# CONVERTER.net
KiCad netlist of a schematic drawn in Altium Designer
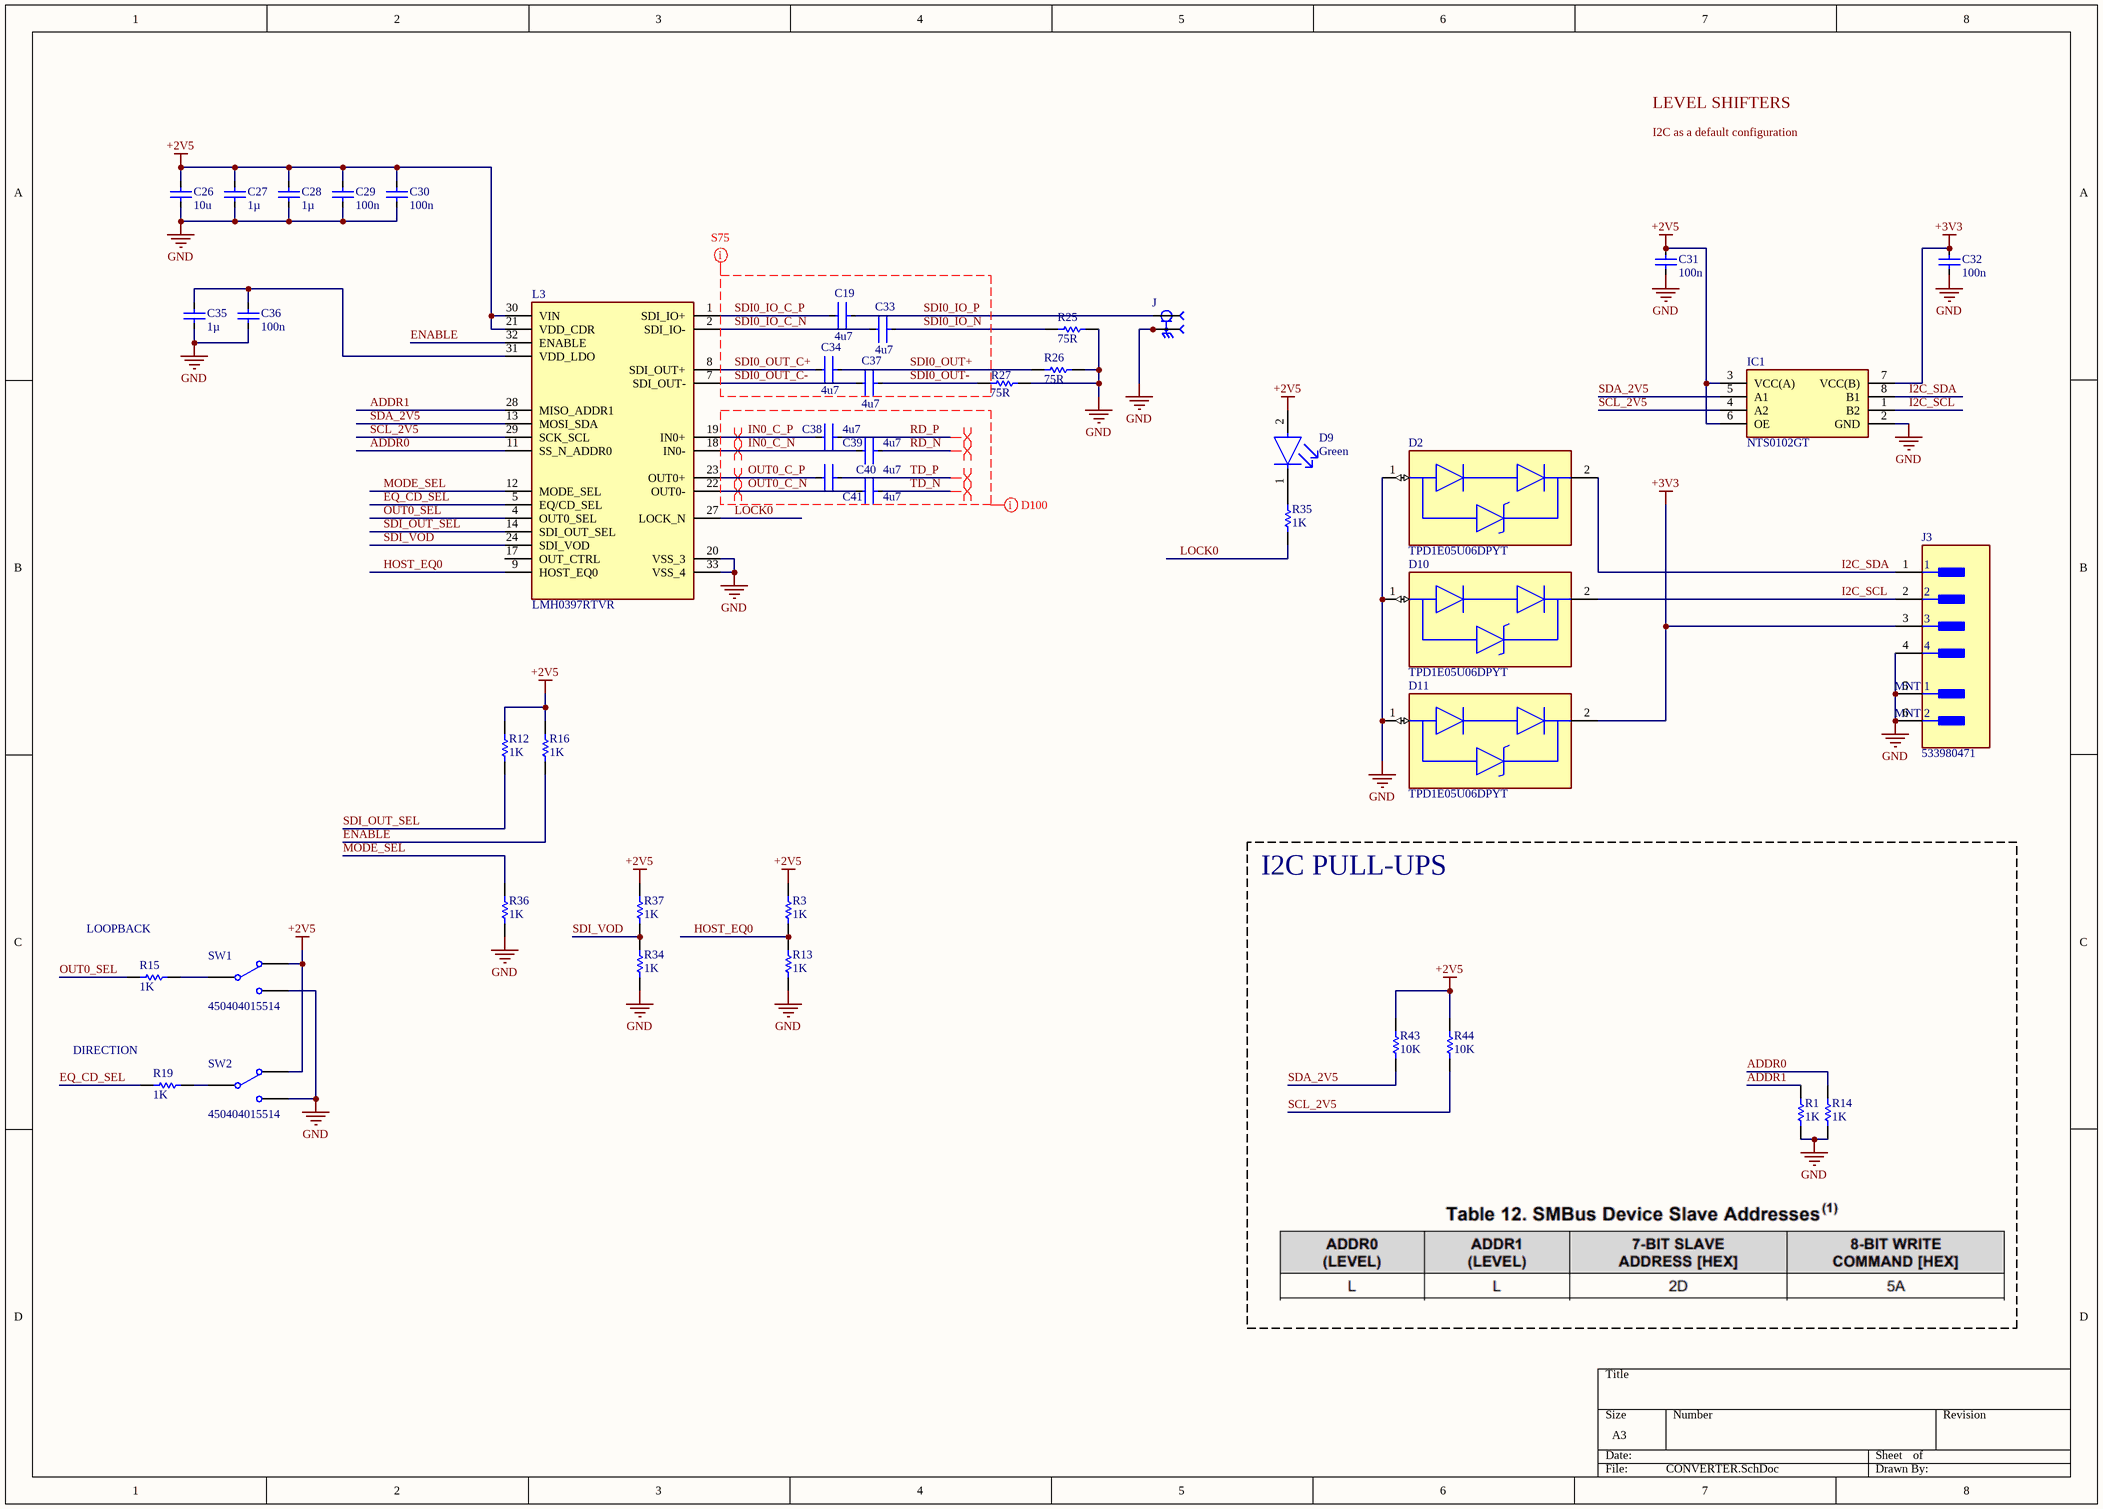
[diagram p0: CONVERTER.SchDoc]

(export (version "E")
  (design (tool "Eeschema 10.0.6"))
  (components
    (comp (ref "C19")
      (value "4u7")
      (footprint "FP-GRM155-0_1-MFG")
      (description "Chip Multilayer Ceramic Capacitors for General Purpose, 0402, 4.7uF, X5R, 15%, 20%, 6.3V")
      (fields (field (name "VOLTAGE") "6.3V") (field (name "TOLERANCE") "20%"))
      (libsource (lib "Altium Content Vault") (part "11868f565c42a9108669ba33697ecf6"))
    )
    (comp (ref "C26")
      (value "10u")
      (footprint "FP-C1608-080-0_1-IPC_C")
      (description "MLCC 10μF ±10% 6.3V JB SMD 0603")
      (fields (field (name "TOLERANCE") "10%") (field (name "Comment") "C1608JB0J106K080AB"))
      (libsource (lib "Schlib1") (part "C1608JB0J106K080AB"))
    )
    (comp (ref "C27")
      (value "1µ")
      (footprint "pcblib1:CAPC1005X55X10NL05")
      (description "MLCC 1 uF, +/- 10%, 10 V, -55 to 85 degC, 0402 (1005 Metric), RoHS, Tape and Reel")
      (fields (field (name "MANUFACTURER") "TDK") (field (name "TOLERANCE") "±10%"))
      (libsource (lib "Schlib1") (part "C1005X5R1A105K050BB"))
    )
    (comp (ref "C28")
      (value "1µ")
      (footprint "pcblib1:CAPC1005X55X10NL05")
      (description "MLCC 1 uF, +/- 10%, 10 V, -55 to 85 degC, 0402 (1005 Metric), RoHS, Tape and Reel")
      (fields (field (name "MANUFACTURER") "TDK") (field (name "TOLERANCE") "±10%"))
      (libsource (lib "Schlib1") (part "C1005X5R1A105K050BB"))
    )
    (comp (ref "C29")
      (value "100n")
      (footprint "FP-C1005-050-0_05-IPC_C")
      (description "MLCC 100nF ±10% 50V X7R SMD 0402")
      (fields (field (name "VOLTAGE") "50V") (field (name "TOLERANCE") "10%"))
      (libsource (lib "Schlib1") (part "C1005X7R1H104K050BB"))
    )
    (comp (ref "C30")
      (value "100n")
      (footprint "FP-C1005-050-0_05-IPC_C")
      (description "MLCC 100nF ±10% 50V X7R SMD 0402")
      (fields (field (name "VOLTAGE") "50V") (field (name "TOLERANCE") "10%"))
      (libsource (lib "Schlib1") (part "C1005X7R1H104K050BB"))
    )
    (comp (ref "C31")
      (value "100n")
      (footprint "FP-C1005-050-0_05-IPC_C")
      (description "MLCC 100nF ±10% 50V X7R SMD 0402")
      (fields (field (name "VOLTAGE") "50V") (field (name "TOLERANCE") "10%"))
      (libsource (lib "Schlib1") (part "C1005X7R1H104K050BB"))
    )
    (comp (ref "C32")
      (value "100n")
      (footprint "FP-C1005-050-0_05-IPC_C")
      (description "MLCC 100nF ±10% 50V X7R SMD 0402")
      (fields (field (name "VOLTAGE") "50V") (field (name "TOLERANCE") "10%"))
      (libsource (lib "Schlib1") (part "C1005X7R1H104K050BB"))
    )
    (comp (ref "C33")
      (value "4u7")
      (footprint "FP-GRM155-0_1-MFG")
      (description "Chip Multilayer Ceramic Capacitors for General Purpose, 0402, 4.7uF, X5R, 15%, 20%, 6.3V")
      (fields (field (name "VOLTAGE") "6.3V") (field (name "TOLERANCE") "20%"))
      (libsource (lib "Altium Content Vault") (part "11868f565c42a9108669ba33697ecf6"))
    )
    (comp (ref "C34")
      (value "4u7")
      (footprint "FP-GRM155-0_1-MFG")
      (description "Chip Multilayer Ceramic Capacitors for General Purpose, 0402, 4.7uF, X5R, 15%, 20%, 6.3V")
      (fields (field (name "VOLTAGE") "6.3V") (field (name "TOLERANCE") "20%"))
      (libsource (lib "Altium Content Vault") (part "11868f565c42a9108669ba33697ecf6"))
    )
    (comp (ref "C35")
      (value "1µ")
      (footprint "pcblib1:CAPC1005X55X10NL05")
      (description "MLCC 1 uF, +/- 10%, 10 V, -55 to 85 degC, 0402 (1005 Metric), RoHS, Tape and Reel")
      (fields (field (name "MANUFACTURER") "TDK") (field (name "TOLERANCE") "±10%"))
      (libsource (lib "Schlib1") (part "C1005X5R1A105K050BB"))
    )
    (comp (ref "C36")
      (value "100n")
      (footprint "FP-C1005-050-0_05-IPC_C")
      (description "MLCC 100nF ±10% 50V X7R SMD 0402")
      (fields (field (name "VOLTAGE") "50V") (field (name "TOLERANCE") "10%"))
      (libsource (lib "Schlib1") (part "C1005X7R1H104K050BB"))
    )
    (comp (ref "C37")
      (value "4u7")
      (footprint "FP-GRM155-0_1-MFG")
      (description "Chip Multilayer Ceramic Capacitors for General Purpose, 0402, 4.7uF, X5R, 15%, 20%, 6.3V")
      (fields (field (name "VOLTAGE") "6.3V") (field (name "TOLERANCE") "20%"))
      (libsource (lib "Altium Content Vault") (part "11868f565c42a9108669ba33697ecf6"))
    )
    (comp (ref "C38")
      (value "4u7")
      (footprint "FP-GRM155-0_1-IPC_B")
      (description "Chip Multilayer Ceramic Capacitors for General Purpose, 0402, 4.7uF, X5R, 15%, 20%, 6.3V")
      (fields (field (name "VOLTAGE") "6.3V") (field (name "TOLERANCE") "20%"))
      (libsource (lib "Altium Content Vault") (part "11868f565c42a9108669ba33697ecf6"))
    )
    (comp (ref "C39")
      (value "4u7")
      (footprint "FP-GRM155-0_1-IPC_B")
      (description "Chip Multilayer Ceramic Capacitors for General Purpose, 0402, 4.7uF, X5R, 15%, 20%, 6.3V")
      (fields (field (name "VOLTAGE") "6.3V") (field (name "TOLERANCE") "20%"))
      (libsource (lib "Altium Content Vault") (part "11868f565c42a9108669ba33697ecf6"))
    )
    (comp (ref "C40")
      (value "4u7")
      (footprint "FP-GRM155-0_1-IPC_B")
      (description "Chip Multilayer Ceramic Capacitors for General Purpose, 0402, 4.7uF, X5R, 15%, 20%, 6.3V")
      (fields (field (name "VOLTAGE") "6.3V") (field (name "TOLERANCE") "20%"))
      (libsource (lib "Altium Content Vault") (part "11868f565c42a9108669ba33697ecf6"))
    )
    (comp (ref "C41")
      (value "4u7")
      (footprint "FP-GRM155-0_1-IPC_B")
      (description "Chip Multilayer Ceramic Capacitors for General Purpose, 0402, 4.7uF, X5R, 15%, 20%, 6.3V")
      (fields (field (name "VOLTAGE") "6.3V") (field (name "TOLERANCE") "20%"))
      (libsource (lib "Altium Content Vault") (part "11868f565c42a9108669ba33697ecf6"))
    )
    (comp (ref "D2")
      (value "TPD1E05U06DPYT")
      (footprint "FP-DPY0002A-MFG")
      (description "TVS DIODE 5.5V 14V 2X1SON")
      (libsource (lib "Altium Content Vault") (part "412d7b51f24ac3502e108348619af9c"))
    )
    (comp (ref "D9")
      (value "LTST-C191GKT")
      (footprint "FP-LTST-C191GKT-MFG")
      (description "LED GREEN CLEAR CHIP SMD")
      (fields (field (name "COLOR") "Green"))
      (libsource (lib "Altium Content Vault") (part "8706943c75ba83719d021d2fdc84c58"))
    )
    (comp (ref "D10")
      (value "TPD1E05U06DPYT")
      (footprint "FP-DPY0002A-MFG")
      (description "TVS DIODE 5.5V 14V 2X1SON")
      (libsource (lib "Altium Content Vault") (part "412d7b51f24ac3502e108348619af9c"))
    )
    (comp (ref "D11")
      (value "TPD1E05U06DPYT")
      (footprint "FP-DPY0002A-MFG")
      (description "TVS DIODE 5.5V 14V 2X1SON")
      (libsource (lib "Altium Content Vault") (part "412d7b51f24ac3502e108348619af9c"))
    )
    (comp (ref "IC1")
      (value "NTS0102GT")
      (footprint "SamacSys:NTS0102GT")
      (description "Integrated Circuit")
      (libsource (lib "Schlib1") (part "NTS0102GT"))
    )
    (comp (ref "J")
      (value "BNC7T-J-P-XX-ST-EM1D")
      (footprint "SAMTEC_BNC7T-J-P-XX-ST-EM1D")
      (description "BNC Connector Jack, Female Socket 75Ohm Board Edge, End Launch; Panel Mount Solder")
      (fields (field (name "MP") "BNC7T-J-P-GN-ST-EM1D") (field (name "MF") "Samtec Inc."))
      (libsource (lib "Schlib1") (part "BNC7T-J-P-XX-ST-EM1D"))
    )
    (comp (ref "J3")
      (value "533980471")
      (footprint "FP-533980471-MFG")
      (description "CONN HEADER SMD 4POS 1.25MM")
      (fields
        (field (name "OCTOPART") "https://octopart.com/53398-0471-molex-655296")
        (field (name "MANUFACTURER") "Molex")
      )
      (libsource (lib "Altium Content Vault") (part "3b6f738a5616415d78381ad43816e4a"))
    )
    (comp (ref "L3")
      (value "LMH0397RTVR")
      (footprint "SamacSys:QFN50P500X500X80-33N-D")
      (description "The LMH0397 is a 3G-SDI 75-Ω bidirectional I/O with integrated reclocker.")
      (fields (field (name "MOUSER PART NUMBER") "595-LMH0397RTVR"))
      (libsource (lib "Schlib1") (part "LMH0397RTVR"))
    )
    (comp (ref "R1")
      (value "1K")
      (footprint "RESC1005X40X25LL05T10")
      (fields
        (field (name "PART NUMBER") "RC0402FR-070RL")
        (field (name "MANUFACTURER") "Yageo / Phycomp")
        (field (name "Comment") "RC0402FR-071KL")
      )
      (libsource (lib "Altium Content Vault") (part "RES"))
    )
    (comp (ref "R3")
      (value "1K")
      (footprint "RESC1005X40X25LL05T10")
      (fields
        (field (name "PART NUMBER") "RC0402FR-070RL")
        (field (name "MANUFACTURER") "Yageo / Phycomp")
        (field (name "Comment") "RC0402FR-071KL")
      )
      (libsource (lib "Altium Content Vault") (part "RES"))
    )
    (comp (ref "R12")
      (value "1K")
      (footprint "RESC1005X40X25LL05T10")
      (fields
        (field (name "PART NUMBER") "RC0402FR-070RL")
        (field (name "MANUFACTURER") "Yageo / Phycomp")
        (field (name "Comment") "RC0402FR-071KL")
      )
      (libsource (lib "Altium Content Vault") (part "RES"))
    )
    (comp (ref "R13")
      (value "1K")
      (footprint "RESC1005X40X25LL05T10")
      (fields
        (field (name "PART NUMBER") "RC0402FR-070RL")
        (field (name "MANUFACTURER") "Yageo / Phycomp")
        (field (name "Comment") "RC0402FR-071KL")
      )
      (libsource (lib "Altium Content Vault") (part "RES"))
    )
    (comp (ref "R14")
      (value "1K")
      (footprint "RESC1005X40X25LL05T10")
      (fields
        (field (name "PART NUMBER") "RC0402FR-070RL")
        (field (name "MANUFACTURER") "Yageo / Phycomp")
        (field (name "Comment") "RC0402FR-071KL")
      )
      (libsource (lib "Altium Content Vault") (part "RES"))
    )
    (comp (ref "R15")
      (value "1K")
      (footprint "RESC1005X40X25LL05T10")
      (fields
        (field (name "PART NUMBER") "RC0402FR-070RL")
        (field (name "MANUFACTURER") "Yageo / Phycomp")
        (field (name "Comment") "RC0402FR-071KL")
      )
      (libsource (lib "Altium Content Vault") (part "RES"))
    )
    (comp (ref "R16")
      (value "1K")
      (footprint "RESC1005X40X25LL05T10")
      (fields
        (field (name "PART NUMBER") "RC0402FR-070RL")
        (field (name "MANUFACTURER") "Yageo / Phycomp")
        (field (name "Comment") "RC0402FR-071KL")
      )
      (libsource (lib "Altium Content Vault") (part "RES"))
    )
    (comp (ref "R19")
      (value "1K")
      (footprint "RESC1005X40X25LL05T10")
      (fields
        (field (name "PART NUMBER") "RC0402FR-070RL")
        (field (name "MANUFACTURER") "Yageo / Phycomp")
        (field (name "Comment") "RC0402FR-071KL")
      )
      (libsource (lib "Altium Content Vault") (part "RES"))
    )
    (comp (ref "R25")
      (value "75R")
      (footprint "RESC1005X40X25LL05T10")
      (fields (field (name "MANUFACTURER") "Yageo / Phycomp") (field (name "PART NUMBER") "RC0402FR-0775RL"))
      (libsource (lib "Altium Content Vault") (part "RES"))
    )
    (comp (ref "R26")
      (value "75R")
      (footprint "RESC1005X40X25LL05T10")
      (fields (field (name "MANUFACTURER") "Yageo / Phycomp") (field (name "PART NUMBER") "RC0402FR-0775RL"))
      (libsource (lib "Altium Content Vault") (part "RES"))
    )
    (comp (ref "R27")
      (value "75R")
      (footprint "RESC1005X40X25LL05T10")
      (fields (field (name "MANUFACTURER") "Yageo / Phycomp") (field (name "PART NUMBER") "RC0402FR-0775RL"))
      (libsource (lib "Altium Content Vault") (part "RES"))
    )
    (comp (ref "R34")
      (value "1K")
      (footprint "RESC1005X40X25LL05T10")
      (fields
        (field (name "PART NUMBER") "RC0402FR-070RL")
        (field (name "MANUFACTURER") "Yageo / Phycomp")
        (field (name "Comment") "RC0402FR-071KL")
      )
      (libsource (lib "Altium Content Vault") (part "RES"))
    )
    (comp (ref "R35")
      (value "1K")
      (footprint "RESC1005X40X25LL05T10")
      (fields
        (field (name "PART NUMBER") "RC0402FR-070RL")
        (field (name "MANUFACTURER") "Yageo / Phycomp")
        (field (name "Comment") "RC0402FR-071KL")
      )
      (libsource (lib "Altium Content Vault") (part "RES"))
    )
    (comp (ref "R36")
      (value "1K")
      (footprint "RESC1005X40X25LL05T10")
      (fields
        (field (name "PART NUMBER") "RC0402FR-070RL")
        (field (name "MANUFACTURER") "Yageo / Phycomp")
        (field (name "Comment") "RC0402FR-071KL")
      )
      (libsource (lib "Altium Content Vault") (part "RES"))
    )
    (comp (ref "R37")
      (value "1K")
      (footprint "RESC1005X40X25LL05T10")
      (fields
        (field (name "PART NUMBER") "RC0402FR-070RL")
        (field (name "MANUFACTURER") "Yageo / Phycomp")
        (field (name "Comment") "RC0402FR-071KL")
      )
      (libsource (lib "Altium Content Vault") (part "RES"))
    )
    (comp (ref "R43")
      (value "10K")
      (footprint "RESC1005X40X25LL05T10")
      (fields (field (name "PART NUMBER") "RC0402FR-0710KL") (field (name "MANUFACTURER") "Yageo / Phycomp"))
      (libsource (lib "Altium Content Vault") (part "RES"))
    )
    (comp (ref "R44")
      (value "10K")
      (footprint "RESC1005X40X25LL05T10")
      (fields (field (name "PART NUMBER") "RC0402FR-0710KL") (field (name "MANUFACTURER") "Yageo / Phycomp"))
      (libsource (lib "Altium Content Vault") (part "RES"))
    )
    (comp (ref "SW1")
      (value "450404015514")
      (footprint "450404015514")
      (description "Slide Switch, 0.3A, 5Vdc, Smd Rohs Compliant: Yes")
      (libsource (lib "Altium Content Vault") (part "SPDT"))
    )
    (comp (ref "SW2")
      (value "450404015514")
      (footprint "450404015514")
      (description "Slide Switch, 0.3A, 5Vdc, Smd Rohs Compliant: Yes")
      (libsource (lib "Altium Content Vault") (part "SPDT"))
    )
  )
  (nets
    (net (code "1") (name "+2V5") (class "Default")
      (node (ref "C26") (pin "1") (pinfunction "1_1") (pintype "passive"))
      (node (ref "C27") (pin "1") (pinfunction "1_1") (pintype "passive"))
      (node (ref "C28") (pin "1") (pinfunction "1_1") (pintype "passive"))
      (node (ref "C29") (pin "1") (pinfunction "1_1") (pintype "passive"))
      (node (ref "C30") (pin "1") (pinfunction "1_1") (pintype "passive"))
      (node (ref "C31") (pin "1") (pinfunction "1_1") (pintype "passive"))
      (node (ref "D9") (pin "2") (pinfunction "A_2") (pintype "passive"))
      (node (ref "IC1") (pin "3") (pinfunction "VCC(A)_3") (pintype "passive"))
      (node (ref "IC1") (pin "6") (pinfunction "OE_6") (pintype "passive"))
      (node (ref "L3") (pin "21") (pinfunction "VDD_CDR_21") (pintype "passive"))
      (node (ref "L3") (pin "30") (pinfunction "VIN_30") (pintype "passive"))
      (node (ref "R12") (pin "1") (pinfunction "1_1") (pintype "passive"))
      (node (ref "R16") (pin "1") (pinfunction "1_1") (pintype "passive"))
      (node (ref "R3") (pin "1") (pinfunction "1_1") (pintype "passive"))
      (node (ref "R37") (pin "1") (pinfunction "1_1") (pintype "passive"))
      (node (ref "R43") (pin "1") (pinfunction "1_1") (pintype "passive"))
      (node (ref "R44") (pin "1") (pinfunction "1_1") (pintype "passive"))
      (node (ref "SW1") (pin "L1") (pinfunction "L1_L1") (pintype "passive"))
      (node (ref "SW2") (pin "L1") (pinfunction "L1_L1") (pintype "passive"))
    )
    (net (code "2") (name "+3V3") (class "Default")
      (node (ref "C32") (pin "1") (pinfunction "1_1") (pintype "passive"))
      (node (ref "D11") (pin "2") (pinfunction "GND_2") (pintype "power_in"))
      (node (ref "IC1") (pin "7") (pinfunction "VCC(B)_7") (pintype "passive"))
      (node (ref "J3") (pin "3") (pinfunction "3_3") (pintype "passive"))
    )
    (net (code "3") (name "/ADDR0") (class "Default")
      (node (ref "L3") (pin "11") (pinfunction "SS_N_ADDR0_11") (pintype "passive"))
      (node (ref "R14") (pin "1") (pinfunction "1_1") (pintype "passive"))
    )
    (net (code "4") (name "/ADDR1") (class "Default")
      (node (ref "L3") (pin "28") (pinfunction "MISO_ADDR1_28") (pintype "passive"))
      (node (ref "R1") (pin "1") (pinfunction "1_1") (pintype "passive"))
    )
    (net (code "5") (name "/ENABLE") (class "Default")
      (node (ref "L3") (pin "32") (pinfunction "ENABLE_32") (pintype "passive"))
      (node (ref "R16") (pin "2") (pinfunction "2_2") (pintype "passive"))
    )
    (net (code "6") (name "/EQ_CD_SEL") (class "Default")
      (node (ref "L3") (pin "5") (pinfunction "EQ/CD_SEL_5") (pintype "passive"))
      (node (ref "R19") (pin "1") (pinfunction "1_1") (pintype "passive"))
    )
    (net (code "7") (name "/HOST_EQ0") (class "Default")
      (node (ref "L3") (pin "9") (pinfunction "HOST_EQ0_9") (pintype "passive"))
      (node (ref "R13") (pin "1") (pinfunction "1_1") (pintype "passive"))
      (node (ref "R3") (pin "2") (pinfunction "2_2") (pintype "passive"))
    )
    (net (code "9") (name "/I2C_SCL") (class "Default")
      (node (ref "D10") (pin "2") (pinfunction "GND_2") (pintype "power_in"))
      (node (ref "IC1") (pin "1") (pinfunction "B2_1") (pintype "passive"))
      (node (ref "J3") (pin "2") (pinfunction "2_2") (pintype "passive"))
    )
    (net (code "10") (name "/I2C_SDA") (class "Default")
      (node (ref "D2") (pin "2") (pinfunction "GND_2") (pintype "power_in"))
      (node (ref "IC1") (pin "8") (pinfunction "B1_8") (pintype "passive"))
      (node (ref "J3") (pin "1") (pinfunction "1_1") (pintype "passive"))
    )
    (net (code "11") (name "/IN0_C_N") (class "Default")
      (node (ref "C39") (pin "2") (pinfunction "2_2") (pintype "passive"))
      (node (ref "L3") (pin "18") (pinfunction "IN0-_18") (pintype "passive"))
    )
    (net (code "12") (name "/IN0_C_P") (class "Default")
      (node (ref "C38") (pin "2") (pinfunction "2_2") (pintype "passive"))
      (node (ref "L3") (pin "19") (pinfunction "IN0+_19") (pintype "passive"))
    )
    (net (code "14") (name "/LOCK0") (class "Default")
      (node (ref "L3") (pin "27") (pinfunction "LOCK_N_27") (pintype "passive"))
      (node (ref "R35") (pin "2") (pinfunction "2_2") (pintype "passive"))
    )
    (net (code "15") (name "/MODE_SEL") (class "Default")
      (node (ref "L3") (pin "12") (pinfunction "MODE_SEL_12") (pintype "passive"))
      (node (ref "R36") (pin "1") (pinfunction "1_1") (pintype "passive"))
    )
    (net (code "16") (name "/OUT0_C_N") (class "Default")
      (node (ref "C41") (pin "2") (pinfunction "2_2") (pintype "passive"))
      (node (ref "L3") (pin "22") (pinfunction "OUT0-_22") (pintype "passive"))
    )
    (net (code "17") (name "/OUT0_C_P") (class "Default")
      (node (ref "C40") (pin "2") (pinfunction "2_2") (pintype "passive"))
      (node (ref "L3") (pin "23") (pinfunction "OUT0+_23") (pintype "passive"))
    )
    (net (code "18") (name "/OUT0_SEL") (class "Default")
      (node (ref "L3") (pin "4") (pinfunction "OUT0_SEL_4") (pintype "passive"))
      (node (ref "R15") (pin "1") (pinfunction "1_1") (pintype "passive"))
    )
    (net (code "19") (name "/RD_N") (class "Default")
      (node (ref "C39") (pin "1") (pinfunction "1_1") (pintype "passive"))
    )
    (net (code "20") (name "/RD_P") (class "Default")
      (node (ref "C38") (pin "1") (pinfunction "1_1") (pintype "passive"))
    )
    (net (code "21") (name "/SCL_2V5") (class "Default")
      (node (ref "IC1") (pin "4") (pinfunction "A2_4") (pintype "passive"))
      (node (ref "L3") (pin "29") (pinfunction "SCK_SCL_29") (pintype "passive"))
      (node (ref "R44") (pin "2") (pinfunction "2_2") (pintype "passive"))
    )
    (net (code "22") (name "/SDA_2V5") (class "Default")
      (node (ref "IC1") (pin "5") (pinfunction "A1_5") (pintype "passive"))
      (node (ref "L3") (pin "13") (pinfunction "MOSI_SDA_13") (pintype "passive"))
      (node (ref "R43") (pin "2") (pinfunction "2_2") (pintype "passive"))
    )
    (net (code "23") (name "/SDI0_IO_C_N") (class "Default")
      (node (ref "C33") (pin "2") (pinfunction "2_2") (pintype "passive"))
      (node (ref "L3") (pin "2") (pinfunction "SDI_IO-_2") (pintype "passive"))
    )
    (net (code "24") (name "/SDI0_IO_C_P") (class "Default")
      (node (ref "C19") (pin "2") (pinfunction "2_2") (pintype "passive"))
      (node (ref "L3") (pin "1") (pinfunction "SDI_IO+_1") (pintype "passive"))
    )
    (net (code "25") (name "/SDI0_IO_N") (class "Default")
      (node (ref "C33") (pin "1") (pinfunction "1_1") (pintype "passive"))
      (node (ref "R25") (pin "1") (pinfunction "1_1") (pintype "passive"))
    )
    (net (code "26") (name "/SDI0_IO_P") (class "Default")
      (node (ref "C19") (pin "1") (pinfunction "1_1") (pintype "passive"))
      (node (ref "J") (pin "1") (pinfunction "1_1") (pintype "passive"))
    )
    (net (code "27") (name "/SDI0_OUT+") (class "Default")
      (node (ref "C34") (pin "1") (pinfunction "1_1") (pintype "passive"))
      (node (ref "R26") (pin "1") (pinfunction "1_1") (pintype "passive"))
    )
    (net (code "28") (name "/SDI0_OUT-") (class "Default")
      (node (ref "C37") (pin "1") (pinfunction "1_1") (pintype "passive"))
      (node (ref "R27") (pin "1") (pinfunction "1_1") (pintype "passive"))
    )
    (net (code "29") (name "/SDI0_OUT_C+") (class "Default")
      (node (ref "C34") (pin "2") (pinfunction "2_2") (pintype "passive"))
      (node (ref "L3") (pin "8") (pinfunction "SDI_OUT+_8") (pintype "passive"))
    )
    (net (code "30") (name "/SDI0_OUT_C-") (class "Default")
      (node (ref "C37") (pin "2") (pinfunction "2_2") (pintype "passive"))
      (node (ref "L3") (pin "7") (pinfunction "SDI_OUT-_7") (pintype "passive"))
    )
    (net (code "31") (name "/SDI_OUT_SEL") (class "Default")
      (node (ref "L3") (pin "14") (pinfunction "SDI_OUT_SEL_14") (pintype "passive"))
      (node (ref "R12") (pin "2") (pinfunction "2_2") (pintype "passive"))
    )
    (net (code "32") (name "/SDI_VOD") (class "Default")
      (node (ref "L3") (pin "24") (pinfunction "SDI_VOD_24") (pintype "passive"))
      (node (ref "R34") (pin "1") (pinfunction "1_1") (pintype "passive"))
      (node (ref "R37") (pin "2") (pinfunction "2_2") (pintype "passive"))
    )
    (net (code "33") (name "/TD_N") (class "Default")
      (node (ref "C41") (pin "1") (pinfunction "1_1") (pintype "passive"))
    )
    (net (code "34") (name "/TD_P") (class "Default")
      (node (ref "C40") (pin "1") (pinfunction "1_1") (pintype "passive"))
    )
    (net (code "35") (name "GND") (class "Default")
      (node (ref "C26") (pin "2") (pinfunction "2_2") (pintype "passive"))
      (node (ref "C27") (pin "2") (pinfunction "2_2") (pintype "passive"))
      (node (ref "C28") (pin "2") (pinfunction "2_2") (pintype "passive"))
      (node (ref "C29") (pin "2") (pinfunction "2_2") (pintype "passive"))
      (node (ref "C30") (pin "2") (pinfunction "2_2") (pintype "passive"))
      (node (ref "C31") (pin "2") (pinfunction "2_2") (pintype "passive"))
      (node (ref "C32") (pin "2") (pinfunction "2_2") (pintype "passive"))
      (node (ref "C35") (pin "2") (pinfunction "2_2") (pintype "passive"))
      (node (ref "C36") (pin "2") (pinfunction "2_2") (pintype "passive"))
      (node (ref "D10") (pin "1") (pinfunction "I/O_1") (pintype "bidirectional"))
      (node (ref "D11") (pin "1") (pinfunction "I/O_1") (pintype "bidirectional"))
      (node (ref "D2") (pin "1") (pinfunction "I/O_1") (pintype "bidirectional"))
      (node (ref "IC1") (pin "2") (pinfunction "GND_2") (pintype "passive"))
      (node (ref "J") (pin "S1") (pinfunction "2_S1") (pintype "passive"))
      (node (ref "J") (pin "S2") (pinfunction "2_S2") (pintype "passive"))
      (node (ref "J") (pin "S3") (pinfunction "2_S3") (pintype "passive"))
      (node (ref "J") (pin "S4") (pinfunction "2_S4") (pintype "passive"))
      (node (ref "J3") (pin "4") (pinfunction "4_4") (pintype "passive"))
      (node (ref "J3") (pin "5") (pinfunction "MNT_1_5") (pintype "passive"))
      (node (ref "J3") (pin "6") (pinfunction "MNT_2_6") (pintype "passive"))
      (node (ref "L3") (pin "20") (pinfunction "VSS_3_20") (pintype "passive"))
      (node (ref "L3") (pin "33") (pinfunction "VSS_4_33") (pintype "passive"))
      (node (ref "R1") (pin "2") (pinfunction "2_2") (pintype "passive"))
      (node (ref "R13") (pin "2") (pinfunction "2_2") (pintype "passive"))
      (node (ref "R14") (pin "2") (pinfunction "2_2") (pintype "passive"))
      (node (ref "R25") (pin "2") (pinfunction "2_2") (pintype "passive"))
      (node (ref "R26") (pin "2") (pinfunction "2_2") (pintype "passive"))
      (node (ref "R27") (pin "2") (pinfunction "2_2") (pintype "passive"))
      (node (ref "R34") (pin "2") (pinfunction "2_2") (pintype "passive"))
      (node (ref "R36") (pin "2") (pinfunction "2_2") (pintype "passive"))
      (node (ref "SW1") (pin "L2") (pinfunction "L2_L2") (pintype "passive"))
      (node (ref "SW2") (pin "L2") (pinfunction "L2_L2") (pintype "passive"))
    )
    (net (code "36") (name "Net-(D9-C)") (class "Default")
      (node (ref "D9") (pin "1") (pinfunction "C_1") (pintype "passive"))
      (node (ref "R35") (pin "1") (pinfunction "1_1") (pintype "passive"))
    )
    (net (code "37") (name "Net-(L3-VDD_LDO)") (class "Default")
      (node (ref "C35") (pin "1") (pinfunction "1_1") (pintype "passive"))
      (node (ref "C36") (pin "1") (pinfunction "1_1") (pintype "passive"))
      (node (ref "L3") (pin "31") (pinfunction "VDD_LDO_31") (pintype "passive"))
    )
    (net (code "38") (name "Net-(R15-Pad2)") (class "Default")
      (node (ref "R15") (pin "2") (pinfunction "2_2") (pintype "passive"))
      (node (ref "SW1") (pin "COM") (pinfunction "COM_COM") (pintype "passive"))
    )
    (net (code "39") (name "Net-(R19-Pad2)") (class "Default")
      (node (ref "R19") (pin "2") (pinfunction "2_2") (pintype "passive"))
      (node (ref "SW2") (pin "COM") (pinfunction "COM_COM") (pintype "passive"))
    )
    (net (code "40") (name "unconnected-(L3-OUT_CTRL-Pad17)") (class "Default")
      (node (ref "L3") (pin "17") (pinfunction "OUT_CTRL_17") (pintype "passive"))
    )
  )
)
